# McPiFace-Environment-V1.net
KiCad netlist of a schematic drawn in EAGLE
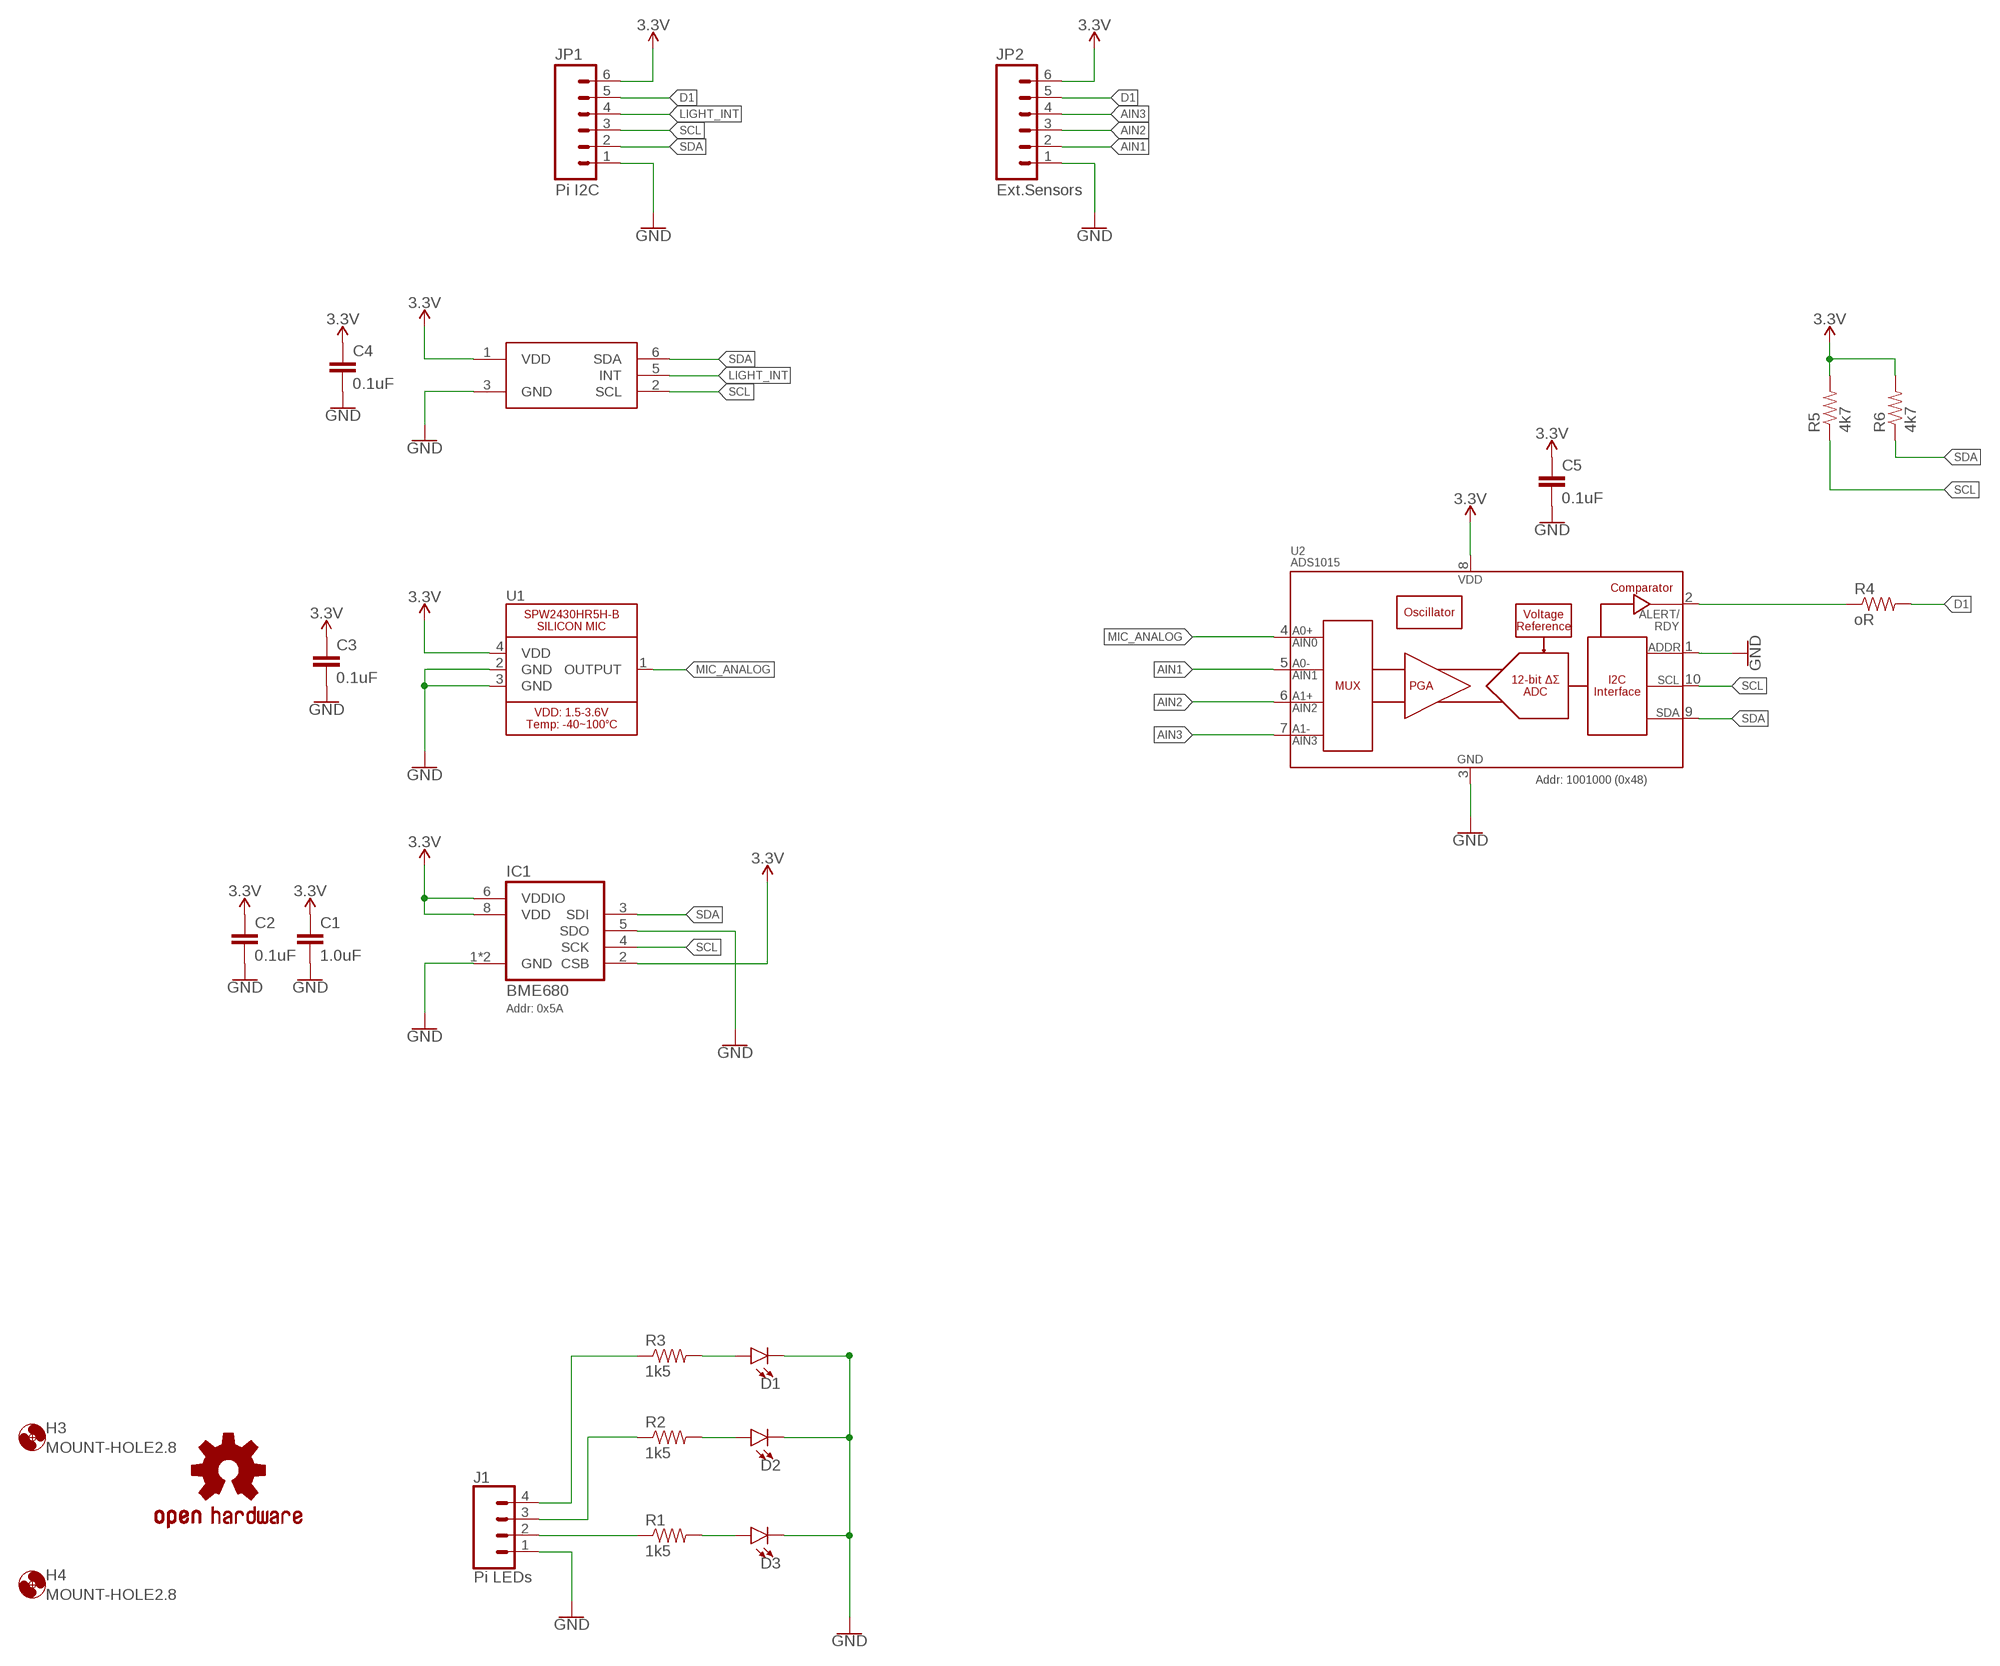
[diagram p0: schematic, sheet 1]

(export (version "E")
  (design (tool "Eeschema 10.0.6"))
  (components
    (comp (ref "C1")
      (value "1.0uF")
      (footprint "eagle-import:0805")
      (libsource (lib "eagle-import") (part "CAP0805"))
    )
    (comp (ref "C2")
      (value "0.1uF")
      (footprint "eagle-import:0805")
      (libsource (lib "eagle-import") (part "CAP0805"))
    )
    (comp (ref "C3")
      (value "0.1uF")
      (footprint "eagle-import:0805")
      (libsource (lib "eagle-import") (part "CAP0805"))
    )
    (comp (ref "C4")
      (value "0.1uF")
      (footprint "eagle-import:0805")
      (libsource (lib "eagle-import") (part "CAP0805"))
    )
    (comp (ref "C5")
      (value "0.1uF")
      (footprint "eagle-import:0805")
      (libsource (lib "eagle-import") (part "CAP0805"))
    )
    (comp (ref "D1")
      (value "LED1206-BOTTOM-1.6MM")
      (footprint "eagle-import:LED-1206-BOTTOM-1.6MM")
      (libsource (lib "eagle-import") (part "LED1206-BOTTOM-1.6MM"))
    )
    (comp (ref "D2")
      (value "LED1206-BOTTOM-1.6MM")
      (footprint "eagle-import:LED-1206-BOTTOM-1.6MM")
      (libsource (lib "eagle-import") (part "LED1206-BOTTOM-1.6MM"))
    )
    (comp (ref "D3")
      (value "LED1206-BOTTOM-1.6MM")
      (footprint "eagle-import:LED-1206-BOTTOM-1.6MM")
      (libsource (lib "eagle-import") (part "LED1206-BOTTOM-1.6MM"))
    )
    (comp (ref "H3")
      (value "MOUNT-HOLE2.8")
      (footprint "eagle-import:2,8")
      (libsource (lib "eagle-import") (part "MOUNT-HOLE2.8"))
    )
    (comp (ref "H4")
      (value "MOUNT-HOLE2.8")
      (footprint "eagle-import:2,8")
      (libsource (lib "eagle-import") (part "MOUNT-HOLE2.8"))
    )
    (comp (ref "IC1")
      (value "BME680")
      (footprint "eagle-import:BME680")
      (libsource (lib "eagle-import") (part "BME680"))
    )
    (comp (ref "J1")
      (value "Pi LEDs")
      (footprint "eagle-import:1X04_1MM_RA")
      (libsource (lib "eagle-import") (part "CONN_04SMD2"))
    )
    (comp (ref "JP1")
      (value "Pi I2C")
      (footprint "eagle-import:1X06-1MM")
      (libsource (lib "eagle-import") (part "M06SMD-1MM"))
    )
    (comp (ref "JP2")
      (value "Ext.Sensors")
      (footprint "eagle-import:1X06-1MM")
      (libsource (lib "eagle-import") (part "M06SMD-1MM"))
    )
    (comp (ref "LOGO1")
      (value "OSHW-LOGOL")
      (footprint "eagle-import:OSHW-LOGO-L")
      (libsource (lib "eagle-import") (part "OSHW-LOGOL"))
    )
    (comp (ref "R1")
      (value "1k5")
      (footprint "eagle-import:0805")
      (libsource (lib "eagle-import") (part "RESISTOR0805-RES"))
    )
    (comp (ref "R2")
      (value "1k5")
      (footprint "eagle-import:0805")
      (libsource (lib "eagle-import") (part "RESISTOR0805-RES"))
    )
    (comp (ref "R3")
      (value "1k5")
      (footprint "eagle-import:0805")
      (libsource (lib "eagle-import") (part "RESISTOR0805-RES"))
    )
    (comp (ref "R4")
      (value "oR")
      (footprint "eagle-import:0805")
      (libsource (lib "eagle-import") (part "RESISTOR0805-RES"))
    )
    (comp (ref "R5")
      (value "4k7")
      (footprint "eagle-import:0805")
      (libsource (lib "eagle-import") (part "RESISTOR0805-RES"))
    )
    (comp (ref "R6")
      (value "4k7")
      (footprint "eagle-import:0805")
      (libsource (lib "eagle-import") (part "RESISTOR0805-RES"))
    )
    (comp (ref "U$1")
      (value "TCS3472")
      (footprint "eagle-import:FN-6")
      (libsource (lib "eagle-import") (part "TCS3472"))
    )
    (comp (ref "U1")
      (value "SPW2430HR5H-B")
      (footprint "eagle-import:SPW2430HR5H-B")
      (libsource (lib "eagle-import") (part "SPW2430HR5H-B"))
    )
    (comp (ref "U2")
      (value "ADS1015")
      (footprint "eagle-import:MSOP10")
      (libsource (lib "eagle-import") (part "ADS1015"))
    )
  )
  (nets
    (net (code "1") (name "3.3V") (class "Default")
      (node (ref "C1") (pin "1") (pinfunction "1_1") (pintype "passive"))
      (node (ref "C2") (pin "1") (pinfunction "1_1") (pintype "passive"))
      (node (ref "C3") (pin "1") (pinfunction "1_1") (pintype "passive"))
      (node (ref "C4") (pin "1") (pinfunction "1_1") (pintype "passive"))
      (node (ref "C5") (pin "1") (pinfunction "1_1") (pintype "passive"))
      (node (ref "IC1") (pin "2") (pinfunction "CSB_2") (pintype "input"))
      (node (ref "IC1") (pin "6") (pinfunction "VDDIO_6") (pintype "power_in"))
      (node (ref "IC1") (pin "8") (pinfunction "VDD_8") (pintype "power_in"))
      (node (ref "JP1") (pin "6") (pinfunction "6_6") (pintype "passive"))
      (node (ref "JP2") (pin "6") (pinfunction "6_6") (pintype "passive"))
      (node (ref "R5") (pin "2") (pinfunction "2_2") (pintype "passive"))
      (node (ref "R6") (pin "2") (pinfunction "2_2") (pintype "passive"))
      (node (ref "U$1") (pin "1") (pinfunction "VDD_1") (pintype "bidirectional"))
      (node (ref "U1") (pin "4") (pinfunction "VDD_4") (pintype "power_in"))
      (node (ref "U2") (pin "8") (pinfunction "VDD_8") (pintype "bidirectional"))
    )
    (net (code "2") (name "AIN1") (class "Default")
      (node (ref "JP2") (pin "2") (pinfunction "2_2") (pintype "passive"))
      (node (ref "U2") (pin "5") (pinfunction "AIN1_5") (pintype "bidirectional"))
    )
    (net (code "3") (name "AIN2") (class "Default")
      (node (ref "JP2") (pin "3") (pinfunction "3_3") (pintype "passive"))
      (node (ref "U2") (pin "6") (pinfunction "AIN2_6") (pintype "bidirectional"))
    )
    (net (code "4") (name "AIN3") (class "Default")
      (node (ref "JP2") (pin "4") (pinfunction "4_4") (pintype "passive"))
      (node (ref "U2") (pin "7") (pinfunction "AIN3_7") (pintype "bidirectional"))
    )
    (net (code "5") (name "D1") (class "Default")
      (node (ref "JP1") (pin "5") (pinfunction "5_5") (pintype "passive"))
      (node (ref "JP2") (pin "5") (pinfunction "5_5") (pintype "passive"))
      (node (ref "R4") (pin "2") (pinfunction "2_2") (pintype "passive"))
    )
    (net (code "6") (name "GND") (class "Default")
      (node (ref "C1") (pin "2") (pinfunction "2_2") (pintype "passive"))
      (node (ref "C2") (pin "2") (pinfunction "2_2") (pintype "passive"))
      (node (ref "C3") (pin "2") (pinfunction "2_2") (pintype "passive"))
      (node (ref "C4") (pin "2") (pinfunction "2_2") (pintype "passive"))
      (node (ref "C5") (pin "2") (pinfunction "2_2") (pintype "passive"))
      (node (ref "D1") (pin "C") (pinfunction "C_C") (pintype "passive"))
      (node (ref "D2") (pin "C") (pinfunction "C_C") (pintype "passive"))
      (node (ref "D3") (pin "C") (pinfunction "C_C") (pintype "passive"))
      (node (ref "IC1") (pin "1") (pinfunction "GND_1") (pintype "power_in"))
      (node (ref "IC1") (pin "5") (pinfunction "SDO_5") (pintype "output"))
      (node (ref "IC1") (pin "7") (pinfunction "GND_7") (pintype "power_in"))
      (node (ref "J1") (pin "1") (pinfunction "1_1") (pintype "passive"))
      (node (ref "JP1") (pin "1") (pinfunction "1_1") (pintype "passive"))
      (node (ref "JP2") (pin "1") (pinfunction "1_1") (pintype "passive"))
      (node (ref "U$1") (pin "3") (pinfunction "GND_3") (pintype "bidirectional"))
      (node (ref "U1") (pin "2") (pinfunction "GND_2") (pintype "power_in"))
      (node (ref "U1") (pin "3") (pinfunction "GND_3") (pintype "power_in"))
      (node (ref "U2") (pin "1") (pinfunction "ADDR_1") (pintype "bidirectional"))
      (node (ref "U2") (pin "3") (pinfunction "VSS_3") (pintype "bidirectional"))
    )
    (net (code "7") (name "LIGHT_INT") (class "Default")
      (node (ref "JP1") (pin "4") (pinfunction "4_4") (pintype "passive"))
      (node (ref "U$1") (pin "5") (pinfunction "INT_5") (pintype "bidirectional"))
    )
    (net (code "8") (name "MIC_ANALOG") (class "Default")
      (node (ref "U1") (pin "1") (pinfunction "OUTPUT_1") (pintype "output"))
      (node (ref "U2") (pin "4") (pinfunction "AIN0_4") (pintype "bidirectional"))
    )
    (net (code "9") (name "Net-(D1-PadA)") (class "Default")
      (node (ref "D1") (pin "A") (pinfunction "A_A") (pintype "passive"))
      (node (ref "R3") (pin "2") (pinfunction "2_2") (pintype "passive"))
    )
    (net (code "10") (name "Net-(D2-PadA)") (class "Default")
      (node (ref "D2") (pin "A") (pinfunction "A_A") (pintype "passive"))
      (node (ref "R2") (pin "2") (pinfunction "2_2") (pintype "passive"))
    )
    (net (code "11") (name "Net-(D3-PadA)") (class "Default")
      (node (ref "D3") (pin "A") (pinfunction "A_A") (pintype "passive"))
      (node (ref "R1") (pin "2") (pinfunction "2_2") (pintype "passive"))
    )
    (net (code "12") (name "Net-(J1-Pad2)") (class "Default")
      (node (ref "J1") (pin "2") (pinfunction "2_2") (pintype "passive"))
      (node (ref "R1") (pin "1") (pinfunction "1_1") (pintype "passive"))
    )
    (net (code "13") (name "Net-(J1-Pad3)") (class "Default")
      (node (ref "J1") (pin "3") (pinfunction "3_3") (pintype "passive"))
      (node (ref "R2") (pin "1") (pinfunction "1_1") (pintype "passive"))
    )
    (net (code "14") (name "Net-(J1-Pad4)") (class "Default")
      (node (ref "J1") (pin "4") (pinfunction "4_4") (pintype "passive"))
      (node (ref "R3") (pin "1") (pinfunction "1_1") (pintype "passive"))
    )
    (net (code "15") (name "Net-(U2-ALERT{slash}RDY)") (class "Default")
      (node (ref "R4") (pin "1") (pinfunction "1_1") (pintype "passive"))
      (node (ref "U2") (pin "2") (pinfunction "ALERT/RDY_2") (pintype "bidirectional"))
    )
    (net (code "16") (name "SCL") (class "Default")
      (node (ref "IC1") (pin "4") (pinfunction "SCK_4") (pintype "input"))
      (node (ref "JP1") (pin "3") (pinfunction "3_3") (pintype "passive"))
      (node (ref "R5") (pin "1") (pinfunction "1_1") (pintype "passive"))
      (node (ref "U$1") (pin "2") (pinfunction "SCL_2") (pintype "bidirectional"))
      (node (ref "U2") (pin "10") (pinfunction "SCL_10") (pintype "bidirectional"))
    )
    (net (code "17") (name "SDA") (class "Default")
      (node (ref "IC1") (pin "3") (pinfunction "SDI_3") (pintype "input"))
      (node (ref "JP1") (pin "2") (pinfunction "2_2") (pintype "passive"))
      (node (ref "R6") (pin "1") (pinfunction "1_1") (pintype "passive"))
      (node (ref "U$1") (pin "6") (pinfunction "SDA_6") (pintype "bidirectional"))
      (node (ref "U2") (pin "9") (pinfunction "SDA_9") (pintype "bidirectional"))
    )
  )
)
